# 09_CONSOLE.net
KiCad netlist of a schematic drawn in Altium Designer
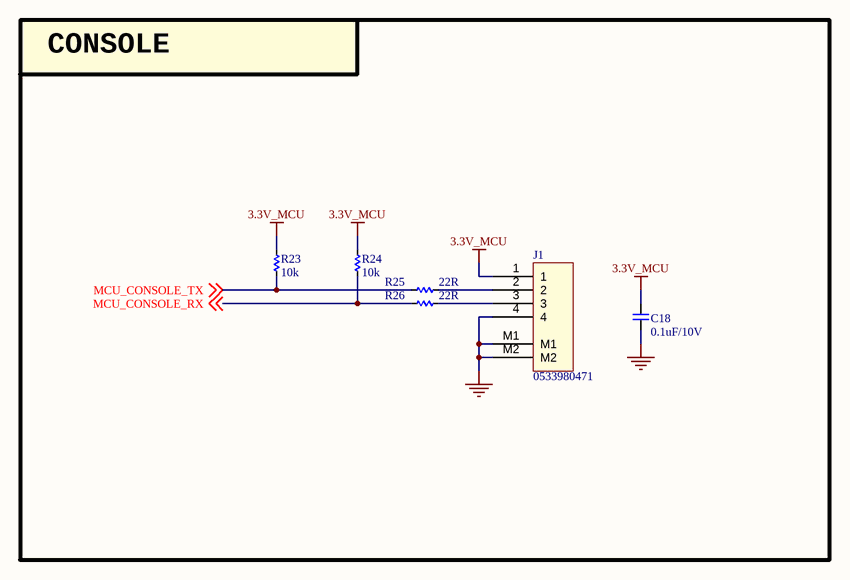
[diagram p0: 09_CONSOLE.SchDoc]

(export (version "E")
  (design (tool "Eeschema 10.0.6"))
  (components
    (comp (ref "C18")
      (value "0.1uF/10V")
      (footprint "CAP_C_1005X50_L")
      (description "CAP")
      (libsource (lib "LABLIB") (part "_CAP_C_2"))
    )
    (comp (ref "J1")
      (value "0533980471")
      (footprint "MOLEX_0533980471")
      (libsource (lib "LABLIB") (part "Header 4x1_2M"))
    )
    (comp (ref "R23")
      (value "10k")
      (footprint "RES_C_1005X40")
      (description "RES")
      (libsource (lib "LABLIB") (part "_RES_B_2"))
    )
    (comp (ref "R24")
      (value "10k")
      (footprint "RES_C_1005X40")
      (description "RES")
      (libsource (lib "LABLIB") (part "_RES_B_2"))
    )
    (comp (ref "R25")
      (value "22R")
      (footprint "RES_C_1005X40")
      (description "RES")
      (libsource (lib "LABLIB") (part "_RES_B_2"))
    )
    (comp (ref "R26")
      (value "22R")
      (footprint "RES_C_1005X40")
      (description "RES")
      (libsource (lib "LABLIB") (part "_RES_B_2"))
    )
  )
  (nets
    (net (code "1") (name "3.3V_MCU") (class "Default")
      (node (ref "C18") (pin "2") (pinfunction "2_2") (pintype "passive"))
      (node (ref "J1") (pin "1") (pinfunction "1_1") (pintype "passive"))
      (node (ref "R23") (pin "2") (pinfunction "2_2") (pintype "passive"))
      (node (ref "R24") (pin "2") (pinfunction "2_2") (pintype "passive"))
    )
    (net (code "2") (name "GND") (class "Default")
      (node (ref "C18") (pin "1") (pinfunction "1_1") (pintype "passive"))
      (node (ref "J1") (pin "4") (pinfunction "4_4") (pintype "passive"))
      (node (ref "J1") (pin "M1") (pinfunction "M1_M1") (pintype "passive"))
      (node (ref "J1") (pin "M2") (pinfunction "M2_M2") (pintype "passive"))
    )
    (net (code "3") (name "MCU_CONSOLE_RX") (class "Default")
      (node (ref "R24") (pin "1") (pinfunction "1_1") (pintype "passive"))
      (node (ref "R26") (pin "2") (pinfunction "2_2") (pintype "passive"))
    )
    (net (code "4") (name "MCU_CONSOLE_TX") (class "Default")
      (node (ref "R23") (pin "1") (pinfunction "1_1") (pintype "passive"))
      (node (ref "R25") (pin "2") (pinfunction "2_2") (pintype "passive"))
    )
    (net (code "5") (name "Net-(J1-Pad2)") (class "Default")
      (node (ref "J1") (pin "2") (pinfunction "2_2") (pintype "passive"))
      (node (ref "R25") (pin "1") (pinfunction "1_1") (pintype "passive"))
    )
    (net (code "6") (name "Net-(J1-Pad3)") (class "Default")
      (node (ref "J1") (pin "3") (pinfunction "3_3") (pintype "passive"))
      (node (ref "R26") (pin "1") (pinfunction "1_1") (pintype "passive"))
    )
  )
)
